# proj_pankov_control_board_1.net
KiCad netlist of a schematic drawn in Altium Designer
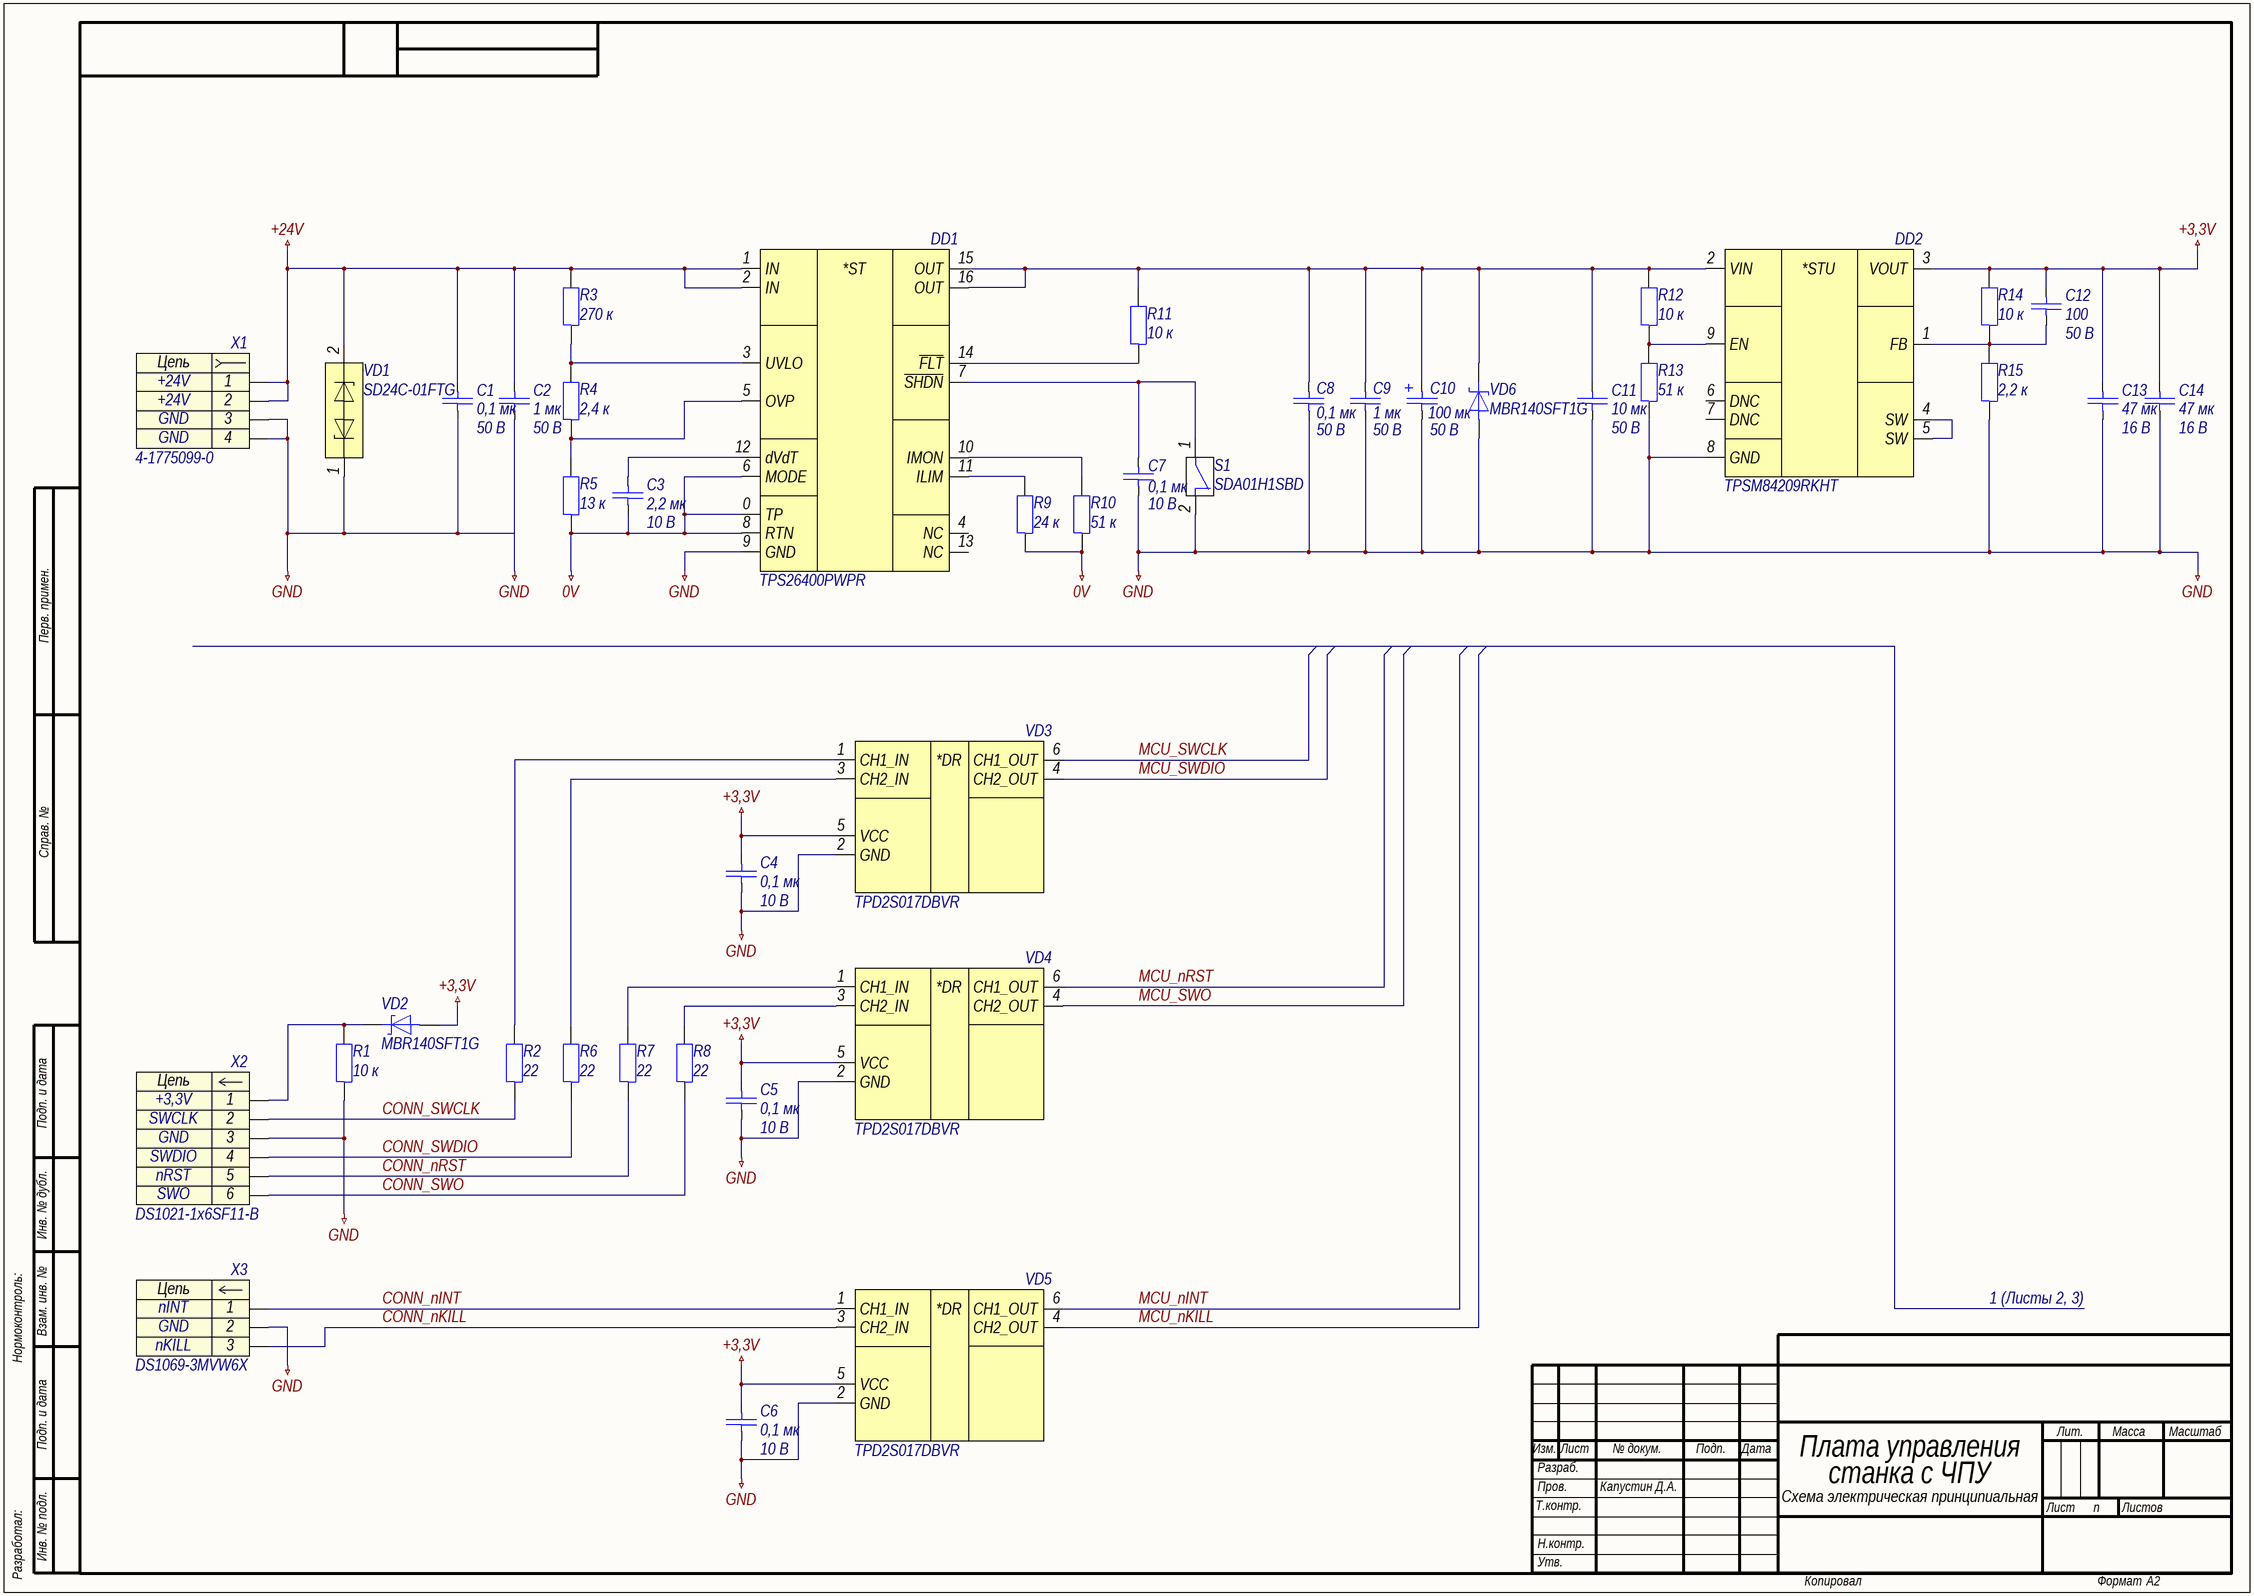
[diagram p0: proj_pankov_control_board_1.SchDoc]

(export (version "E")
  (design (tool "Eeschema 10.0.6"))
  (components
    (comp (ref "C1")
      (value "0,1 мк")
      (footprint "C0603")
      (description "=Описание")
      (fields (field (name "НАПРЯЖЕНИЕ") "50 В"))
      (libsource (lib "Database_Students") (part "CAPACITOR-NONPOLAR"))
    )
    (comp (ref "C2")
      (value "1 мк")
      (footprint "C0603")
      (description "=Описание")
      (fields (field (name "НАПРЯЖЕНИЕ") "50 В"))
      (libsource (lib "Database_Students") (part "CAPACITOR-NONPOLAR"))
    )
    (comp (ref "C3")
      (value "2,2 мк")
      (footprint "C0603")
      (description "=Описание")
      (fields (field (name "НАПРЯЖЕНИЕ") "10 В"))
      (libsource (lib "Database_Students") (part "CAPACITOR-NONPOLAR"))
    )
    (comp (ref "C4")
      (value "0,1 мк")
      (footprint "C0603")
      (description "=Описание")
      (fields (field (name "НАПРЯЖЕНИЕ") "10 В"))
      (libsource (lib "Database_Students") (part "CAPACITOR-NONPOLAR"))
    )
    (comp (ref "C5")
      (value "0,1 мк")
      (footprint "C0603")
      (description "=Описание")
      (fields (field (name "НАПРЯЖЕНИЕ") "10 В"))
      (libsource (lib "Database_Students") (part "CAPACITOR-NONPOLAR"))
    )
    (comp (ref "C6")
      (value "0,1 мк")
      (footprint "C0603")
      (description "=Описание")
      (fields (field (name "НАПРЯЖЕНИЕ") "10 В"))
      (libsource (lib "Database_Students") (part "CAPACITOR-NONPOLAR"))
    )
    (comp (ref "C7")
      (value "0,1 мк")
      (footprint "C0603")
      (description "=Описание")
      (fields (field (name "НАПРЯЖЕНИЕ") "10 В"))
      (libsource (lib "Database_Students") (part "CAPACITOR-NONPOLAR"))
    )
    (comp (ref "C8")
      (value "0,1 мк")
      (footprint "C0603")
      (description "=Описание")
      (fields (field (name "НАПРЯЖЕНИЕ") "50 В"))
      (libsource (lib "Database_Students") (part "CAPACITOR-NONPOLAR"))
    )
    (comp (ref "C9")
      (value "1 мк")
      (footprint "C0603")
      (description "=Описание")
      (fields (field (name "НАПРЯЖЕНИЕ") "50 В"))
      (libsource (lib "Database_Students") (part "CAPACITOR-NONPOLAR"))
    )
    (comp (ref "C10")
      (value "100 мк")
      (footprint "CAPAE-660X660X800")
      (description "=Описание")
      (fields (field (name "НАПРЯЖЕНИЕ") "50 В"))
      (libsource (lib "Database_Students") (part "CAPACITOR-POLAR"))
    )
    (comp (ref "C11")
      (value "10 мк")
      (footprint "C1206")
      (description "=Описание")
      (fields (field (name "НАПРЯЖЕНИЕ") "50 В"))
      (libsource (lib "Database_Students") (part "CAPACITOR-NONPOLAR"))
    )
    (comp (ref "C12")
      (value "100")
      (footprint "C0603")
      (description "=Описание")
      (fields (field (name "НАПРЯЖЕНИЕ") "50 В"))
      (libsource (lib "Database_Students") (part "CAPACITOR-NONPOLAR"))
    )
    (comp (ref "C13")
      (value "47 мк")
      (footprint "C1206")
      (description "=Описание")
      (fields (field (name "НАПРЯЖЕНИЕ") "16 В"))
      (libsource (lib "Database_Students") (part "CAPACITOR-NONPOLAR"))
    )
    (comp (ref "C14")
      (value "47 мк")
      (footprint "C1206")
      (description "=Описание")
      (fields (field (name "НАПРЯЖЕНИЕ") "16 В"))
      (libsource (lib "Database_Students") (part "CAPACITOR-NONPOLAR"))
    )
    (comp (ref "DD1")
      (value "TPS26400PWPR")
      (footprint "HTSSOP-16-P65-500X440X120-L63X25-T246X266")
      (description "=Описание")
      (libsource (lib "Database_Students") (part "TPS26400PWPR"))
    )
    (comp (ref "DD2")
      (value "TPSM84209RKHT")
      (footprint "QFN-FCMOD-9-P65-450X400X210")
      (description "=Описание")
      (libsource (lib "Database_Students") (part "TPSM84209RKHT"))
    )
    (comp (ref "R1")
      (value "10 к")
      (footprint "R0603")
      (description "=Описание")
      (libsource (lib "Database_Students") (part "RESISTOR-COMMON"))
    )
    (comp (ref "R2")
      (value "22")
      (footprint "R0603")
      (description "=Описание")
      (libsource (lib "Database_Students") (part "RESISTOR-COMMON"))
    )
    (comp (ref "R3")
      (value "270 к")
      (footprint "R0603")
      (description "=Описание")
      (libsource (lib "Database_Students") (part "RESISTOR-COMMON"))
    )
    (comp (ref "R4")
      (value "2,4 к")
      (footprint "R0603")
      (description "=Описание")
      (libsource (lib "Database_Students") (part "RESISTOR-COMMON"))
    )
    (comp (ref "R5")
      (value "13 к")
      (footprint "R0603")
      (description "=Описание")
      (libsource (lib "Database_Students") (part "RESISTOR-COMMON"))
    )
    (comp (ref "R6")
      (value "22")
      (footprint "R0603")
      (description "=Описание")
      (libsource (lib "Database_Students") (part "RESISTOR-COMMON"))
    )
    (comp (ref "R7")
      (value "22")
      (footprint "R0603")
      (description "=Описание")
      (libsource (lib "Database_Students") (part "RESISTOR-COMMON"))
    )
    (comp (ref "R8")
      (value "22")
      (footprint "R0603")
      (description "=Описание")
      (libsource (lib "Database_Students") (part "RESISTOR-COMMON"))
    )
    (comp (ref "R9")
      (value "24 к")
      (footprint "R0603")
      (description "=Описание")
      (libsource (lib "Database_Students") (part "RESISTOR-COMMON"))
    )
    (comp (ref "R10")
      (value "51 к")
      (footprint "R0603")
      (description "=Описание")
      (libsource (lib "Database_Students") (part "RESISTOR-COMMON"))
    )
    (comp (ref "R11")
      (value "10 к")
      (footprint "R0603")
      (description "=Описание")
      (libsource (lib "Database_Students") (part "RESISTOR-COMMON"))
    )
    (comp (ref "R12")
      (value "10 к")
      (footprint "R0603")
      (description "=Описание")
      (libsource (lib "Database_Students") (part "RESISTOR-COMMON"))
    )
    (comp (ref "R13")
      (value "51 к")
      (footprint "R0603")
      (description "=Описание")
      (libsource (lib "Database_Students") (part "RESISTOR-COMMON"))
    )
    (comp (ref "R14")
      (value "10 к")
      (footprint "R0603")
      (description "=Описание")
      (libsource (lib "Database_Students") (part "RESISTOR-COMMON"))
    )
    (comp (ref "R15")
      (value "2,2 к")
      (footprint "R0603")
      (description "=Описание")
      (libsource (lib "Database_Students") (part "RESISTOR-COMMON"))
    )
    (comp (ref "S1")
      (value "SDA01H1SBD")
      (footprint "SDA01H1SBD")
      (description "=Описание")
      (libsource (lib "Database_Students") (part "SWITCH-2C"))
    )
    (comp (ref "VD1")
      (value "SD24C-01FTG")
      (footprint "SOD-323-257X130X114")
      (description "=Описание")
      (libsource (lib "Database_Students") (part "ZENER-BI-DIRECTIONAL"))
    )
    (comp (ref "VD2")
      (value "MBR140SFT1G")
      (footprint "SOD-123FL-370X165X98")
      (description "=Описание")
      (libsource (lib "Database_Students") (part "DIODE-SCHOTTKY"))
    )
    (comp (ref "VD3")
      (value "TPD2S017DBVR")
      (footprint "SOT-23-6-P95-290X280X145")
      (description "=Описание")
      (libsource (lib "Database_Students") (part "TPD2S017DBVR"))
    )
    (comp (ref "VD4")
      (value "TPD2S017DBVR")
      (footprint "SOT-23-6-P95-290X280X145")
      (description "=Описание")
      (libsource (lib "Database_Students") (part "TPD2S017DBVR"))
    )
    (comp (ref "VD5")
      (value "TPD2S017DBVR")
      (footprint "SOT-23-6-P95-290X280X145")
      (description "=Описание")
      (libsource (lib "Database_Students") (part "TPD2S017DBVR"))
    )
    (comp (ref "VD6")
      (value "MBR140SFT1G")
      (footprint "SOD-123FL-370X165X98")
      (description "=Описание")
      (libsource (lib "Database_Students") (part "DIODE-SCHOTTKY"))
    )
    (comp (ref "X1")
      (value "4-1775099-0")
      (footprint "4-1775099-0")
      (description "=Описание")
      (libsource (lib "Database_Students") (part "HEADER-4-SCT"))
    )
    (comp (ref "X2")
      (value "DS1021-1x6SF11-B")
      (footprint "DS1021-1X6SF11-B")
      (description "=Описание")
      (libsource (lib "Database_Students") (part "HEADER-6-PLG"))
    )
    (comp (ref "X3")
      (value "DS1069-3MVW6X")
      (footprint "DS1069-3MVW6X")
      (description "=Описание")
      (libsource (lib "Database_Students") (part "HEADER-3-PLG"))
    )
  )
  (nets
    (net (code "1") (name "+3,3V") (class "Default")
      (node (ref "C12") (pin "1") (pinfunction "1_1") (pintype "passive"))
      (node (ref "C13") (pin "1") (pinfunction "1_1") (pintype "passive"))
      (node (ref "C14") (pin "1") (pinfunction "1_1") (pintype "passive"))
      (node (ref "C4") (pin "1") (pinfunction "1_1") (pintype "passive"))
      (node (ref "C5") (pin "1") (pinfunction "1_1") (pintype "passive"))
      (node (ref "C6") (pin "1") (pinfunction "1_1") (pintype "passive"))
      (node (ref "DD2") (pin "3") (pinfunction "VOUT_3") (pintype "passive"))
      (node (ref "R14") (pin "2") (pinfunction "2_2") (pintype "passive"))
      (node (ref "VD2") (pin "2") (pinfunction "2_2") (pintype "passive"))
      (node (ref "VD3") (pin "5") (pinfunction "VCC_5") (pintype "passive"))
      (node (ref "VD4") (pin "5") (pinfunction "VCC_5") (pintype "passive"))
      (node (ref "VD5") (pin "5") (pinfunction "VCC_5") (pintype "passive"))
    )
    (net (code "2") (name "+24V") (class "Default")
      (node (ref "C1") (pin "1") (pinfunction "1_1") (pintype "passive"))
      (node (ref "C2") (pin "1") (pinfunction "1_1") (pintype "passive"))
      (node (ref "DD1") (pin "1") (pinfunction "IN_1") (pintype "passive"))
      (node (ref "DD1") (pin "2") (pinfunction "IN_2") (pintype "passive"))
      (node (ref "R3") (pin "2") (pinfunction "2_2") (pintype "passive"))
      (node (ref "VD1") (pin "2") (pinfunction "2_2") (pintype "passive"))
      (node (ref "X1") (pin "1") (pinfunction "1_1") (pintype "passive"))
      (node (ref "X1") (pin "2") (pinfunction "2_2") (pintype "passive"))
    )
    (net (code "3") (name "/CONN_SWCLK") (class "Default")
      (node (ref "R2") (pin "1") (pinfunction "1_1") (pintype "passive"))
      (node (ref "X2") (pin "2") (pinfunction "2_2") (pintype "passive"))
    )
    (net (code "4") (name "/CONN_SWDIO") (class "Default")
      (node (ref "R6") (pin "1") (pinfunction "1_1") (pintype "passive"))
      (node (ref "X2") (pin "4") (pinfunction "4_4") (pintype "passive"))
    )
    (net (code "5") (name "/CONN_SWO") (class "Default")
      (node (ref "R8") (pin "1") (pinfunction "1_1") (pintype "passive"))
      (node (ref "X2") (pin "6") (pinfunction "6_6") (pintype "passive"))
    )
    (net (code "6") (name "/CONN_nINT") (class "Default")
      (node (ref "VD5") (pin "1") (pinfunction "CH1_IN_1") (pintype "passive"))
      (node (ref "X3") (pin "1") (pinfunction "1_1") (pintype "passive"))
    )
    (net (code "7") (name "/CONN_nKILL") (class "Default")
      (node (ref "VD5") (pin "3") (pinfunction "CH2_IN_3") (pintype "passive"))
      (node (ref "X3") (pin "3") (pinfunction "3_3") (pintype "passive"))
    )
    (net (code "8") (name "/CONN_nRST") (class "Default")
      (node (ref "R7") (pin "1") (pinfunction "1_1") (pintype "passive"))
      (node (ref "X2") (pin "5") (pinfunction "5_5") (pintype "passive"))
    )
    (net (code "9") (name "/MCU_SWCLK") (class "Default")
      (node (ref "VD3") (pin "6") (pinfunction "CH1_OUT_6") (pintype "passive"))
    )
    (net (code "10") (name "/MCU_SWDIO") (class "Default")
      (node (ref "VD3") (pin "4") (pinfunction "CH2_OUT_4") (pintype "passive"))
    )
    (net (code "11") (name "/MCU_SWO") (class "Default")
      (node (ref "VD4") (pin "4") (pinfunction "CH2_OUT_4") (pintype "passive"))
    )
    (net (code "12") (name "/MCU_nINT") (class "Default")
      (node (ref "VD5") (pin "6") (pinfunction "CH1_OUT_6") (pintype "passive"))
    )
    (net (code "13") (name "/MCU_nKILL") (class "Default")
      (node (ref "VD5") (pin "4") (pinfunction "CH2_OUT_4") (pintype "passive"))
    )
    (net (code "14") (name "/MCU_nRST") (class "Default")
      (node (ref "VD4") (pin "6") (pinfunction "CH1_OUT_6") (pintype "passive"))
    )
    (net (code "15") (name "0V") (class "Default")
      (node (ref "C3") (pin "2") (pinfunction "2_2") (pintype "passive"))
      (node (ref "DD1") (pin "0") (pinfunction "TP_0") (pintype "passive"))
      (node (ref "DD1") (pin "6") (pinfunction "MODE_6") (pintype "passive"))
      (node (ref "DD1") (pin "8") (pinfunction "RTN_8") (pintype "passive"))
      (node (ref "R10") (pin "1") (pinfunction "1_1") (pintype "passive"))
      (node (ref "R5") (pin "1") (pinfunction "1_1") (pintype "passive"))
      (node (ref "R9") (pin "1") (pinfunction "1_1") (pintype "passive"))
    )
    (net (code "16") (name "GND") (class "Default")
      (node (ref "C1") (pin "2") (pinfunction "2_2") (pintype "passive"))
      (node (ref "C10") (pin "2") (pinfunction "2_2") (pintype "passive"))
      (node (ref "C11") (pin "2") (pinfunction "2_2") (pintype "passive"))
      (node (ref "C13") (pin "2") (pinfunction "2_2") (pintype "passive"))
      (node (ref "C14") (pin "2") (pinfunction "2_2") (pintype "passive"))
      (node (ref "C2") (pin "2") (pinfunction "2_2") (pintype "passive"))
      (node (ref "C4") (pin "2") (pinfunction "2_2") (pintype "passive"))
      (node (ref "C5") (pin "2") (pinfunction "2_2") (pintype "passive"))
      (node (ref "C6") (pin "2") (pinfunction "2_2") (pintype "passive"))
      (node (ref "C7") (pin "2") (pinfunction "2_2") (pintype "passive"))
      (node (ref "C8") (pin "2") (pinfunction "2_2") (pintype "passive"))
      (node (ref "C9") (pin "2") (pinfunction "2_2") (pintype "passive"))
      (node (ref "DD1") (pin "9") (pinfunction "GND_9") (pintype "passive"))
      (node (ref "DD2") (pin "8") (pinfunction "GND_8") (pintype "passive"))
      (node (ref "R1") (pin "1") (pinfunction "1_1") (pintype "passive"))
      (node (ref "R13") (pin "1") (pinfunction "1_1") (pintype "passive"))
      (node (ref "R15") (pin "1") (pinfunction "1_1") (pintype "passive"))
      (node (ref "S1") (pin "2") (pinfunction "2_2") (pintype "passive"))
      (node (ref "VD1") (pin "1") (pinfunction "1_1") (pintype "passive"))
      (node (ref "VD3") (pin "2") (pinfunction "GND_2") (pintype "passive"))
      (node (ref "VD4") (pin "2") (pinfunction "GND_2") (pintype "passive"))
      (node (ref "VD5") (pin "2") (pinfunction "GND_2") (pintype "passive"))
      (node (ref "VD6") (pin "2") (pinfunction "2_2") (pintype "passive"))
      (node (ref "X1") (pin "3") (pinfunction "3_3") (pintype "passive"))
      (node (ref "X1") (pin "4") (pinfunction "4_4") (pintype "passive"))
      (node (ref "X2") (pin "3") (pinfunction "3_3") (pintype "passive"))
      (node (ref "X3") (pin "2") (pinfunction "2_2") (pintype "passive"))
    )
    (net (code "17") (name "Net-(DD1-ILIM)") (class "Default")
      (node (ref "DD1") (pin "11") (pinfunction "ILIM_11") (pintype "passive"))
      (node (ref "R9") (pin "2") (pinfunction "2_2") (pintype "passive"))
    )
    (net (code "18") (name "Net-(DD1-IMON)") (class "Default")
      (node (ref "DD1") (pin "10") (pinfunction "IMON_10") (pintype "passive"))
      (node (ref "R10") (pin "2") (pinfunction "2_2") (pintype "passive"))
    )
    (net (code "19") (name "Net-(DD1-OVP)") (class "Default")
      (node (ref "DD1") (pin "5") (pinfunction "OVP_5") (pintype "passive"))
      (node (ref "R4") (pin "1") (pinfunction "1_1") (pintype "passive"))
      (node (ref "R5") (pin "2") (pinfunction "2_2") (pintype "passive"))
    )
    (net (code "20") (name "Net-(DD1-UVLO)") (class "Default")
      (node (ref "DD1") (pin "3") (pinfunction "UVLO_3") (pintype "passive"))
      (node (ref "R3") (pin "1") (pinfunction "1_1") (pintype "passive"))
      (node (ref "R4") (pin "2") (pinfunction "2_2") (pintype "passive"))
    )
    (net (code "21") (name "Net-(DD1-dVdT)") (class "Default")
      (node (ref "C3") (pin "1") (pinfunction "1_1") (pintype "passive"))
      (node (ref "DD1") (pin "12") (pinfunction "dVdT_12") (pintype "passive"))
    )
    (net (code "22") (name "Net-(DD1-~{FLT})") (class "Default")
      (node (ref "DD1") (pin "14") (pinfunction "~{FLT}_14") (pintype "passive"))
      (node (ref "R11") (pin "1") (pinfunction "1_1") (pintype "passive"))
    )
    (net (code "23") (name "Net-(DD1-~{SHDN})") (class "Default")
      (node (ref "C7") (pin "1") (pinfunction "1_1") (pintype "passive"))
      (node (ref "DD1") (pin "7") (pinfunction "~{SHDN}_7") (pintype "passive"))
      (node (ref "S1") (pin "1") (pinfunction "1_1") (pintype "passive"))
    )
    (net (code "24") (name "Net-(DD2-EN)") (class "Default")
      (node (ref "DD2") (pin "9") (pinfunction "EN_9") (pintype "passive"))
      (node (ref "R12") (pin "1") (pinfunction "1_1") (pintype "passive"))
      (node (ref "R13") (pin "2") (pinfunction "2_2") (pintype "passive"))
    )
    (net (code "25") (name "Net-(DD2-FB)") (class "Default")
      (node (ref "C12") (pin "2") (pinfunction "2_2") (pintype "passive"))
      (node (ref "DD2") (pin "1") (pinfunction "FB_1") (pintype "passive"))
      (node (ref "R14") (pin "1") (pinfunction "1_1") (pintype "passive"))
      (node (ref "R15") (pin "2") (pinfunction "2_2") (pintype "passive"))
    )
    (net (code "26") (name "Net-(DD2-SW-Pad4)") (class "Default")
      (node (ref "DD2") (pin "4") (pinfunction "SW_4") (pintype "passive"))
      (node (ref "DD2") (pin "5") (pinfunction "SW_5") (pintype "passive"))
    )
    (net (code "27") (name "Net-(DD2-VIN)") (class "Default")
      (node (ref "C10") (pin "1") (pinfunction "1_1") (pintype "passive"))
      (node (ref "C11") (pin "1") (pinfunction "1_1") (pintype "passive"))
      (node (ref "C8") (pin "1") (pinfunction "1_1") (pintype "passive"))
      (node (ref "C9") (pin "1") (pinfunction "1_1") (pintype "passive"))
      (node (ref "DD1") (pin "15") (pinfunction "OUT_15") (pintype "passive"))
      (node (ref "DD1") (pin "16") (pinfunction "OUT_16") (pintype "passive"))
      (node (ref "DD2") (pin "2") (pinfunction "VIN_2") (pintype "passive"))
      (node (ref "R11") (pin "2") (pinfunction "2_2") (pintype "passive"))
      (node (ref "R12") (pin "2") (pinfunction "2_2") (pintype "passive"))
      (node (ref "VD6") (pin "1") (pinfunction "1_1") (pintype "passive"))
    )
    (net (code "28") (name "Net-(R1-Pad2)") (class "Default")
      (node (ref "R1") (pin "2") (pinfunction "2_2") (pintype "passive"))
      (node (ref "VD2") (pin "1") (pinfunction "1_1") (pintype "passive"))
      (node (ref "X2") (pin "1") (pinfunction "1_1") (pintype "passive"))
    )
    (net (code "29") (name "Net-(VD3-CH1_IN)") (class "Default")
      (node (ref "R2") (pin "2") (pinfunction "2_2") (pintype "passive"))
      (node (ref "VD3") (pin "1") (pinfunction "CH1_IN_1") (pintype "passive"))
    )
    (net (code "30") (name "Net-(VD3-CH2_IN)") (class "Default")
      (node (ref "R6") (pin "2") (pinfunction "2_2") (pintype "passive"))
      (node (ref "VD3") (pin "3") (pinfunction "CH2_IN_3") (pintype "passive"))
    )
    (net (code "31") (name "Net-(VD4-CH1_IN)") (class "Default")
      (node (ref "R7") (pin "2") (pinfunction "2_2") (pintype "passive"))
      (node (ref "VD4") (pin "1") (pinfunction "CH1_IN_1") (pintype "passive"))
    )
    (net (code "32") (name "Net-(VD4-CH2_IN)") (class "Default")
      (node (ref "R8") (pin "2") (pinfunction "2_2") (pintype "passive"))
      (node (ref "VD4") (pin "3") (pinfunction "CH2_IN_3") (pintype "passive"))
    )
    (net (code "33") (name "unconnected-(DD1-NC-Pad4)") (class "Default")
      (node (ref "DD1") (pin "4") (pinfunction "NC_4") (pintype "passive"))
    )
    (net (code "34") (name "unconnected-(DD1-NC-Pad13)") (class "Default")
      (node (ref "DD1") (pin "13") (pinfunction "NC_13") (pintype "passive"))
    )
    (net (code "35") (name "unconnected-(DD2-DNC-Pad6)") (class "Default")
      (node (ref "DD2") (pin "6") (pinfunction "DNC_6") (pintype "passive"))
    )
    (net (code "36") (name "unconnected-(DD2-DNC-Pad7)") (class "Default")
      (node (ref "DD2") (pin "7") (pinfunction "DNC_7") (pintype "passive"))
    )
  )
)
